# Chronos-Pad-EasyEDApro-Save.net
KiCad netlist of a schematic drawn in EasyEDA Pro
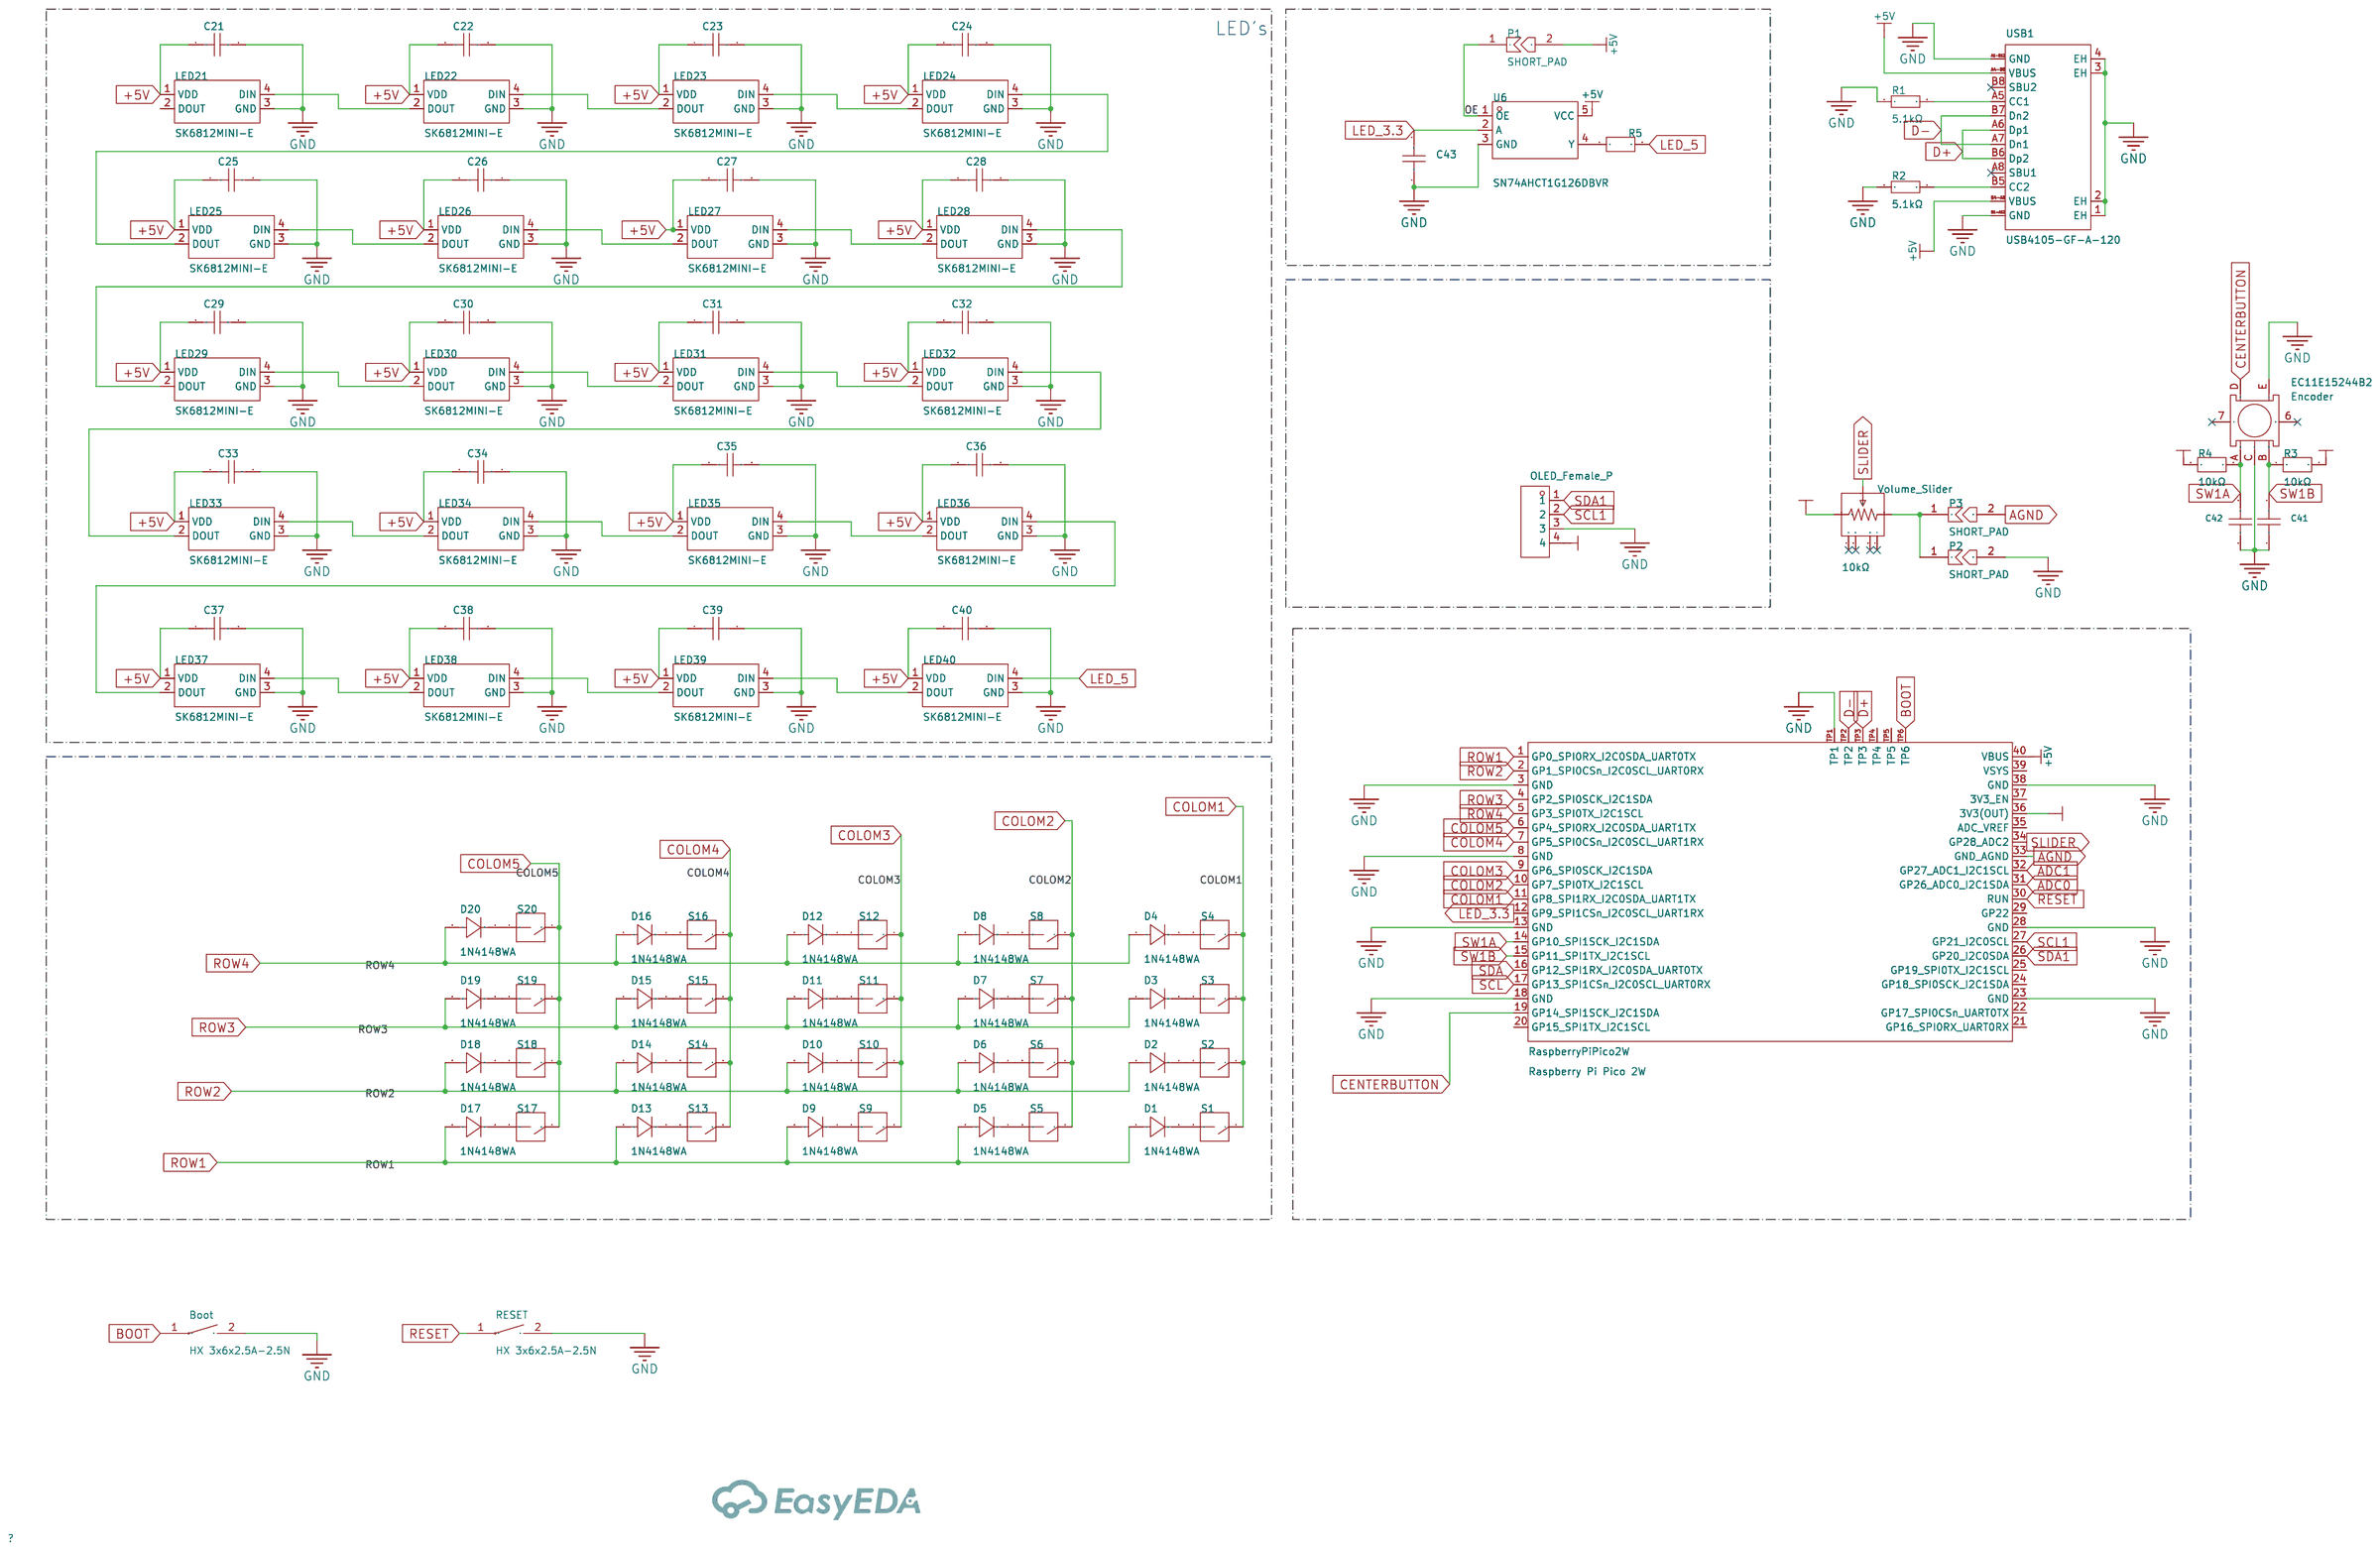
[diagram p0: schematic sheet]

(export (version "E")
  (design (tool "Eeschema 10.0.6"))
  (components
    (comp (ref "Boot")
      (value "HX 3x6x2.5A-2.5N")
      (footprint "easyedapro:SW-SMD_HX-TS-1101-C-W")
      (fields (field (name "Manufacturer") "hanxia(韩下)"))
      (libsource (lib "easyedapro") (part "HX TS-1101-C-W"))
    )
    (comp (ref "C21")
      (value "100nF")
      (footprint "easyedapro:C0603")
      (description "Capacitance:100nF Tolerance:±10% Tolerance:±10% Voltage Rating:50V Temperature Coefficient:X7R")
      (fields
        (field (name "Manufacturer Part") "CC0805KRX7R9BB104")
        (field (name "Manufacturer") "YAGEO(国巨)")
      )
      (libsource (lib "easyedapro") (part "NL0603B104M500CPBN"))
    )
    (comp (ref "C22")
      (value "100nF")
      (footprint "easyedapro:C0603")
      (description "Capacitance:100nF Tolerance:±10% Tolerance:±10% Voltage Rating:50V Temperature Coefficient:X7R")
      (fields
        (field (name "Manufacturer Part") "CC0805KRX7R9BB104")
        (field (name "Manufacturer") "YAGEO(国巨)")
      )
      (libsource (lib "easyedapro") (part "NL0603B104M500CPBN"))
    )
    (comp (ref "C23")
      (value "100nF")
      (footprint "easyedapro:C0603")
      (description "Capacitance:100nF Tolerance:±10% Tolerance:±10% Voltage Rating:50V Temperature Coefficient:X7R")
      (fields
        (field (name "Manufacturer Part") "CC0805KRX7R9BB104")
        (field (name "Manufacturer") "YAGEO(国巨)")
      )
      (libsource (lib "easyedapro") (part "NL0603B104M500CPBN"))
    )
    (comp (ref "C24")
      (value "100nF")
      (footprint "easyedapro:C0603")
      (description "Capacitance:100nF Tolerance:±10% Tolerance:±10% Voltage Rating:50V Temperature Coefficient:X7R")
      (fields
        (field (name "Manufacturer Part") "CC0805KRX7R9BB104")
        (field (name "Manufacturer") "YAGEO(国巨)")
      )
      (libsource (lib "easyedapro") (part "NL0603B104M500CPBN"))
    )
    (comp (ref "C25")
      (value "100nF")
      (footprint "easyedapro:C0603")
      (description "Capacitance:100nF Tolerance:±10% Tolerance:±10% Voltage Rating:50V Temperature Coefficient:X7R")
      (fields
        (field (name "Manufacturer Part") "CC0805KRX7R9BB104")
        (field (name "Manufacturer") "YAGEO(国巨)")
      )
      (libsource (lib "easyedapro") (part "NL0603B104M500CPBN"))
    )
    (comp (ref "C26")
      (value "100nF")
      (footprint "easyedapro:C0603")
      (description "Capacitance:100nF Tolerance:±10% Tolerance:±10% Voltage Rating:50V Temperature Coefficient:X7R")
      (fields
        (field (name "Manufacturer Part") "CC0805KRX7R9BB104")
        (field (name "Manufacturer") "YAGEO(国巨)")
      )
      (libsource (lib "easyedapro") (part "NL0603B104M500CPBN"))
    )
    (comp (ref "C27")
      (value "100nF")
      (footprint "easyedapro:C0603")
      (description "Capacitance:100nF Tolerance:±10% Tolerance:±10% Voltage Rating:50V Temperature Coefficient:X7R")
      (fields
        (field (name "Manufacturer Part") "CC0805KRX7R9BB104")
        (field (name "Manufacturer") "YAGEO(国巨)")
      )
      (libsource (lib "easyedapro") (part "NL0603B104M500CPBN"))
    )
    (comp (ref "C28")
      (value "100nF")
      (footprint "easyedapro:C0603")
      (description "Capacitance:100nF Tolerance:±10% Tolerance:±10% Voltage Rating:50V Temperature Coefficient:X7R")
      (fields
        (field (name "Manufacturer Part") "CC0805KRX7R9BB104")
        (field (name "Manufacturer") "YAGEO(国巨)")
      )
      (libsource (lib "easyedapro") (part "NL0603B104M500CPBN"))
    )
    (comp (ref "C29")
      (value "100nF")
      (footprint "easyedapro:C0603")
      (description "Capacitance:100nF Tolerance:±10% Tolerance:±10% Voltage Rating:50V Temperature Coefficient:X7R")
      (fields
        (field (name "Manufacturer Part") "CC0805KRX7R9BB104")
        (field (name "Manufacturer") "YAGEO(国巨)")
      )
      (libsource (lib "easyedapro") (part "NL0603B104M500CPBN"))
    )
    (comp (ref "C30")
      (value "100nF")
      (footprint "easyedapro:C0603")
      (description "Capacitance:100nF Tolerance:±10% Tolerance:±10% Voltage Rating:50V Temperature Coefficient:X7R")
      (fields
        (field (name "Manufacturer Part") "CC0805KRX7R9BB104")
        (field (name "Manufacturer") "YAGEO(国巨)")
      )
      (libsource (lib "easyedapro") (part "NL0603B104M500CPBN"))
    )
    (comp (ref "C31")
      (value "100nF")
      (footprint "easyedapro:C0603")
      (description "Capacitance:100nF Tolerance:±10% Tolerance:±10% Voltage Rating:50V Temperature Coefficient:X7R")
      (fields
        (field (name "Manufacturer Part") "CC0805KRX7R9BB104")
        (field (name "Manufacturer") "YAGEO(国巨)")
      )
      (libsource (lib "easyedapro") (part "NL0603B104M500CPBN"))
    )
    (comp (ref "C32")
      (value "100nF")
      (footprint "easyedapro:C0603")
      (description "Capacitance:100nF Tolerance:±10% Tolerance:±10% Voltage Rating:50V Temperature Coefficient:X7R")
      (fields
        (field (name "Manufacturer Part") "CC0805KRX7R9BB104")
        (field (name "Manufacturer") "YAGEO(国巨)")
      )
      (libsource (lib "easyedapro") (part "NL0603B104M500CPBN"))
    )
    (comp (ref "C33")
      (value "100nF")
      (footprint "easyedapro:C0603")
      (description "Capacitance:100nF Tolerance:±10% Tolerance:±10% Voltage Rating:50V Temperature Coefficient:X7R")
      (fields
        (field (name "Manufacturer Part") "CC0805KRX7R9BB104")
        (field (name "Manufacturer") "YAGEO(国巨)")
      )
      (libsource (lib "easyedapro") (part "NL0603B104M500CPBN"))
    )
    (comp (ref "C34")
      (value "100nF")
      (footprint "easyedapro:C0603")
      (description "Capacitance:100nF Tolerance:±10% Tolerance:±10% Voltage Rating:50V Temperature Coefficient:X7R")
      (fields
        (field (name "Manufacturer Part") "CC0805KRX7R9BB104")
        (field (name "Manufacturer") "YAGEO(国巨)")
      )
      (libsource (lib "easyedapro") (part "NL0603B104M500CPBN"))
    )
    (comp (ref "C35")
      (value "100nF")
      (footprint "easyedapro:C0603")
      (description "Capacitance:100nF Tolerance:±10% Tolerance:±10% Voltage Rating:50V Temperature Coefficient:X7R")
      (fields
        (field (name "Manufacturer Part") "CC0805KRX7R9BB104")
        (field (name "Manufacturer") "YAGEO(国巨)")
      )
      (libsource (lib "easyedapro") (part "NL0603B104M500CPBN"))
    )
    (comp (ref "C36")
      (value "100nF")
      (footprint "easyedapro:C0603")
      (description "Capacitance:100nF Tolerance:±10% Tolerance:±10% Voltage Rating:50V Temperature Coefficient:X7R")
      (fields
        (field (name "Manufacturer Part") "CC0805KRX7R9BB104")
        (field (name "Manufacturer") "YAGEO(国巨)")
      )
      (libsource (lib "easyedapro") (part "NL0603B104M500CPBN"))
    )
    (comp (ref "C37")
      (value "100nF")
      (footprint "easyedapro:C0603")
      (description "Capacitance:100nF Tolerance:±10% Tolerance:±10% Voltage Rating:50V Temperature Coefficient:X7R")
      (fields
        (field (name "Manufacturer Part") "CC0805KRX7R9BB104")
        (field (name "Manufacturer") "YAGEO(国巨)")
      )
      (libsource (lib "easyedapro") (part "NL0603B104M500CPBN"))
    )
    (comp (ref "C38")
      (value "100nF")
      (footprint "easyedapro:C0603")
      (description "Capacitance:100nF Tolerance:±10% Tolerance:±10% Voltage Rating:50V Temperature Coefficient:X7R")
      (fields
        (field (name "Manufacturer Part") "CC0805KRX7R9BB104")
        (field (name "Manufacturer") "YAGEO(国巨)")
      )
      (libsource (lib "easyedapro") (part "NL0603B104M500CPBN"))
    )
    (comp (ref "C39")
      (value "100nF")
      (footprint "easyedapro:C0603")
      (description "Capacitance:100nF Tolerance:±10% Tolerance:±10% Voltage Rating:50V Temperature Coefficient:X7R")
      (fields
        (field (name "Manufacturer Part") "CC0805KRX7R9BB104")
        (field (name "Manufacturer") "YAGEO(国巨)")
      )
      (libsource (lib "easyedapro") (part "NL0603B104M500CPBN"))
    )
    (comp (ref "C40")
      (value "100nF")
      (footprint "easyedapro:C0603")
      (description "Capacitance:100nF Tolerance:±10% Tolerance:±10% Voltage Rating:50V Temperature Coefficient:X7R")
      (fields
        (field (name "Manufacturer Part") "CC0805KRX7R9BB104")
        (field (name "Manufacturer") "YAGEO(国巨)")
      )
      (libsource (lib "easyedapro") (part "NL0603B104M500CPBN"))
    )
    (comp (ref "C41")
      (value "100nF")
      (footprint "easyedapro:C0805")
      (description "Capacitance:100nF Tolerance:±10% Tolerance:±10% Voltage Rating:50V Temperature Coefficient:X7R")
      (fields
        (field (name "Manufacturer Part") "CC0805KRX7R9BB104")
        (field (name "Manufacturer") "YAGEO(国巨)")
      )
      (libsource (lib "easyedapro") (part "CC0805JRX7R9BB103"))
    )
    (comp (ref "C42")
      (value "100nF")
      (footprint "easyedapro:C0805")
      (description "Capacitance:100nF Tolerance:±10% Tolerance:±10% Voltage Rating:50V Temperature Coefficient:X7R")
      (fields
        (field (name "Manufacturer Part") "CC0805KRX7R9BB104")
        (field (name "Manufacturer") "YAGEO(国巨)")
      )
      (libsource (lib "easyedapro") (part "CC0805JRX7R9BB103"))
    )
    (comp (ref "C43")
      (value "100nF")
      (footprint "easyedapro:C0603")
      (description "Capacitance:100nF Tolerance:±10% Tolerance:±10% Voltage Rating:50V Temperature Coefficient:X7R")
      (fields
        (field (name "Manufacturer Part") "CC0805KRX7R9BB104")
        (field (name "Manufacturer") "YAGEO(国巨)")
      )
      (libsource (lib "easyedapro") (part "NL0603B104M500CPBN"))
    )
    (comp (ref "D1")
      (value "1N4148WA")
      (footprint "easyedapro:SOD-323_L1.7-W1.3-LS2.7-RD")
      (fields (field (name "Manufacturer") "PJSEMI(平晶微)"))
      (libsource (lib "easyedapro") (part "1N4148WS_C5381436"))
    )
    (comp (ref "D2")
      (value "1N4148WA")
      (footprint "easyedapro:SOD-323_L1.7-W1.3-LS2.7-RD")
      (fields (field (name "Manufacturer") "PJSEMI(平晶微)"))
      (libsource (lib "easyedapro") (part "1N4148WS_C5381436"))
    )
    (comp (ref "D3")
      (value "1N4148WA")
      (footprint "easyedapro:SOD-323_L1.7-W1.3-LS2.7-RD")
      (fields (field (name "Manufacturer") "PJSEMI(平晶微)"))
      (libsource (lib "easyedapro") (part "1N4148WS_C5381436"))
    )
    (comp (ref "D4")
      (value "1N4148WA")
      (footprint "easyedapro:SOD-323_L1.7-W1.3-LS2.7-RD")
      (fields (field (name "Manufacturer") "PJSEMI(平晶微)"))
      (libsource (lib "easyedapro") (part "1N4148WS_C5381436"))
    )
    (comp (ref "D5")
      (value "1N4148WA")
      (footprint "easyedapro:SOD-323_L1.7-W1.3-LS2.7-RD")
      (fields (field (name "Manufacturer") "PJSEMI(平晶微)"))
      (libsource (lib "easyedapro") (part "1N4148WS_C5381436"))
    )
    (comp (ref "D6")
      (value "1N4148WA")
      (footprint "easyedapro:SOD-323_L1.7-W1.3-LS2.7-RD")
      (fields (field (name "Manufacturer") "PJSEMI(平晶微)"))
      (libsource (lib "easyedapro") (part "1N4148WS_C5381436"))
    )
    (comp (ref "D7")
      (value "1N4148WA")
      (footprint "easyedapro:SOD-323_L1.7-W1.3-LS2.7-RD")
      (fields (field (name "Manufacturer") "PJSEMI(平晶微)"))
      (libsource (lib "easyedapro") (part "1N4148WS_C5381436"))
    )
    (comp (ref "D8")
      (value "1N4148WA")
      (footprint "easyedapro:SOD-323_L1.7-W1.3-LS2.7-RD")
      (fields (field (name "Manufacturer") "PJSEMI(平晶微)"))
      (libsource (lib "easyedapro") (part "1N4148WS_C5381436"))
    )
    (comp (ref "D9")
      (value "1N4148WA")
      (footprint "easyedapro:SOD-323_L1.7-W1.3-LS2.7-RD")
      (fields (field (name "Manufacturer") "PJSEMI(平晶微)"))
      (libsource (lib "easyedapro") (part "1N4148WS_C5381436"))
    )
    (comp (ref "D10")
      (value "1N4148WA")
      (footprint "easyedapro:SOD-323_L1.7-W1.3-LS2.7-RD")
      (fields (field (name "Manufacturer") "PJSEMI(平晶微)"))
      (libsource (lib "easyedapro") (part "1N4148WS_C5381436"))
    )
    (comp (ref "D11")
      (value "1N4148WA")
      (footprint "easyedapro:SOD-323_L1.7-W1.3-LS2.7-RD")
      (fields (field (name "Manufacturer") "PJSEMI(平晶微)"))
      (libsource (lib "easyedapro") (part "1N4148WS_C5381436"))
    )
    (comp (ref "D12")
      (value "1N4148WA")
      (footprint "easyedapro:SOD-323_L1.7-W1.3-LS2.7-RD")
      (fields (field (name "Manufacturer") "PJSEMI(平晶微)"))
      (libsource (lib "easyedapro") (part "1N4148WS_C5381436"))
    )
    (comp (ref "D13")
      (value "1N4148WA")
      (footprint "easyedapro:SOD-323_L1.7-W1.3-LS2.7-RD")
      (fields (field (name "Manufacturer") "PJSEMI(平晶微)"))
      (libsource (lib "easyedapro") (part "1N4148WS_C5381436"))
    )
    (comp (ref "D14")
      (value "1N4148WA")
      (footprint "easyedapro:SOD-323_L1.7-W1.3-LS2.7-RD")
      (fields (field (name "Manufacturer") "PJSEMI(平晶微)"))
      (libsource (lib "easyedapro") (part "1N4148WS_C5381436"))
    )
    (comp (ref "D15")
      (value "1N4148WA")
      (footprint "easyedapro:SOD-323_L1.7-W1.3-LS2.7-RD")
      (fields (field (name "Manufacturer") "PJSEMI(平晶微)"))
      (libsource (lib "easyedapro") (part "1N4148WS_C5381436"))
    )
    (comp (ref "D16")
      (value "1N4148WA")
      (footprint "easyedapro:SOD-323_L1.7-W1.3-LS2.7-RD")
      (fields (field (name "Manufacturer") "PJSEMI(平晶微)"))
      (libsource (lib "easyedapro") (part "1N4148WS_C5381436"))
    )
    (comp (ref "D17")
      (value "1N4148WA")
      (footprint "easyedapro:SOD-323_L1.7-W1.3-LS2.7-RD")
      (fields (field (name "Manufacturer") "PJSEMI(平晶微)"))
      (libsource (lib "easyedapro") (part "1N4148WS_C5381436"))
    )
    (comp (ref "D18")
      (value "1N4148WA")
      (footprint "easyedapro:SOD-323_L1.7-W1.3-LS2.7-RD")
      (fields (field (name "Manufacturer") "PJSEMI(平晶微)"))
      (libsource (lib "easyedapro") (part "1N4148WS_C5381436"))
    )
    (comp (ref "D19")
      (value "1N4148WA")
      (footprint "easyedapro:SOD-323_L1.7-W1.3-LS2.7-RD")
      (fields (field (name "Manufacturer") "PJSEMI(平晶微)"))
      (libsource (lib "easyedapro") (part "1N4148WS_C5381436"))
    )
    (comp (ref "D20")
      (value "1N4148WA")
      (footprint "easyedapro:SOD-323_L1.7-W1.3-LS2.7-RD")
      (fields (field (name "Manufacturer") "PJSEMI(平晶微)"))
      (libsource (lib "easyedapro") (part "1N4148WS_C5381436"))
    )
    (comp (ref "Encoder")
      (value "EC11E15244B2")
      (footprint "easyedapro:SW-TH_EC11XXXXXXXX")
      (fields (field (name "Manufacturer") "ALPSALPINE(阿尔卑斯阿尔派)"))
      (libsource (lib "easyedapro") (part "EC11E15204A3"))
    )
    (comp (ref "LED21")
      (value "SK6812MINI-E")
      (footprint "easyedapro:LED-SMD_L3.2-W2.8-LS5.9_SK6812MINI-E")
      (fields (field (name "Manufacturer") "欧思科光电"))
      (libsource (lib "easyedapro") (part "SK6812MINI-E_C5149201"))
    )
    (comp (ref "LED22")
      (value "SK6812MINI-E")
      (footprint "easyedapro:LED-SMD_L3.2-W2.8-LS5.9_SK6812MINI-E")
      (fields (field (name "Manufacturer") "欧思科光电"))
      (libsource (lib "easyedapro") (part "SK6812MINI-E_C5149201"))
    )
    (comp (ref "LED23")
      (value "SK6812MINI-E")
      (footprint "easyedapro:LED-SMD_L3.2-W2.8-LS5.9_SK6812MINI-E")
      (fields (field (name "Manufacturer") "欧思科光电"))
      (libsource (lib "easyedapro") (part "SK6812MINI-E_C5149201"))
    )
    (comp (ref "LED24")
      (value "SK6812MINI-E")
      (footprint "easyedapro:LED-SMD_L3.2-W2.8-LS5.9_SK6812MINI-E")
      (fields (field (name "Manufacturer") "欧思科光电"))
      (libsource (lib "easyedapro") (part "SK6812MINI-E_C5149201"))
    )
    (comp (ref "LED25")
      (value "SK6812MINI-E")
      (footprint "easyedapro:LED-SMD_L3.2-W2.8-LS5.9_SK6812MINI-E")
      (fields (field (name "Manufacturer") "欧思科光电"))
      (libsource (lib "easyedapro") (part "SK6812MINI-E_C5149201"))
    )
    (comp (ref "LED26")
      (value "SK6812MINI-E")
      (footprint "easyedapro:LED-SMD_L3.2-W2.8-LS5.9_SK6812MINI-E")
      (fields (field (name "Manufacturer") "欧思科光电"))
      (libsource (lib "easyedapro") (part "SK6812MINI-E_C5149201"))
    )
    (comp (ref "LED27")
      (value "SK6812MINI-E")
      (footprint "easyedapro:LED-SMD_L3.2-W2.8-LS5.9_SK6812MINI-E")
      (fields (field (name "Manufacturer") "欧思科光电"))
      (libsource (lib "easyedapro") (part "SK6812MINI-E_C5149201"))
    )
    (comp (ref "LED28")
      (value "SK6812MINI-E")
      (footprint "easyedapro:LED-SMD_L3.2-W2.8-LS5.9_SK6812MINI-E")
      (fields (field (name "Manufacturer") "欧思科光电"))
      (libsource (lib "easyedapro") (part "SK6812MINI-E_C5149201"))
    )
    (comp (ref "LED29")
      (value "SK6812MINI-E")
      (footprint "easyedapro:LED-SMD_L3.2-W2.8-LS5.9_SK6812MINI-E")
      (fields (field (name "Manufacturer") "欧思科光电"))
      (libsource (lib "easyedapro") (part "SK6812MINI-E_C5149201"))
    )
    (comp (ref "LED30")
      (value "SK6812MINI-E")
      (footprint "easyedapro:LED-SMD_L3.2-W2.8-LS5.9_SK6812MINI-E")
      (fields (field (name "Manufacturer") "欧思科光电"))
      (libsource (lib "easyedapro") (part "SK6812MINI-E_C5149201"))
    )
    (comp (ref "LED31")
      (value "SK6812MINI-E")
      (footprint "easyedapro:LED-SMD_L3.2-W2.8-LS5.9_SK6812MINI-E")
      (fields (field (name "Manufacturer") "欧思科光电"))
      (libsource (lib "easyedapro") (part "SK6812MINI-E_C5149201"))
    )
    (comp (ref "LED32")
      (value "SK6812MINI-E")
      (footprint "easyedapro:LED-SMD_L3.2-W2.8-LS5.9_SK6812MINI-E")
      (fields (field (name "Manufacturer") "欧思科光电"))
      (libsource (lib "easyedapro") (part "SK6812MINI-E_C5149201"))
    )
    (comp (ref "LED33")
      (value "SK6812MINI-E")
      (footprint "easyedapro:LED-SMD_L3.2-W2.8-LS5.9_SK6812MINI-E")
      (fields (field (name "Manufacturer") "欧思科光电"))
      (libsource (lib "easyedapro") (part "SK6812MINI-E_C5149201"))
    )
    (comp (ref "LED34")
      (value "SK6812MINI-E")
      (footprint "easyedapro:LED-SMD_L3.2-W2.8-LS5.9_SK6812MINI-E")
      (fields (field (name "Manufacturer") "欧思科光电"))
      (libsource (lib "easyedapro") (part "SK6812MINI-E_C5149201"))
    )
    (comp (ref "LED35")
      (value "SK6812MINI-E")
      (footprint "easyedapro:LED-SMD_L3.2-W2.8-LS5.9_SK6812MINI-E")
      (fields (field (name "Manufacturer") "欧思科光电"))
      (libsource (lib "easyedapro") (part "SK6812MINI-E_C5149201"))
    )
    (comp (ref "LED36")
      (value "SK6812MINI-E")
      (footprint "easyedapro:LED-SMD_L3.2-W2.8-LS5.9_SK6812MINI-E")
      (fields (field (name "Manufacturer") "欧思科光电"))
      (libsource (lib "easyedapro") (part "SK6812MINI-E_C5149201"))
    )
    (comp (ref "LED37")
      (value "SK6812MINI-E")
      (footprint "easyedapro:LED-SMD_L3.2-W2.8-LS5.9_SK6812MINI-E")
      (fields (field (name "Manufacturer") "欧思科光电"))
      (libsource (lib "easyedapro") (part "SK6812MINI-E_C5149201"))
    )
    (comp (ref "LED38")
      (value "SK6812MINI-E")
      (footprint "easyedapro:LED-SMD_L3.2-W2.8-LS5.9_SK6812MINI-E")
      (fields (field (name "Manufacturer") "欧思科光电"))
      (libsource (lib "easyedapro") (part "SK6812MINI-E_C5149201"))
    )
    (comp (ref "LED39")
      (value "SK6812MINI-E")
      (footprint "easyedapro:LED-SMD_L3.2-W2.8-LS5.9_SK6812MINI-E")
      (fields (field (name "Manufacturer") "欧思科光电"))
      (libsource (lib "easyedapro") (part "SK6812MINI-E_C5149201"))
    )
    (comp (ref "LED40")
      (value "SK6812MINI-E")
      (footprint "easyedapro:LED-SMD_L3.2-W2.8-LS5.9_SK6812MINI-E")
      (fields (field (name "Manufacturer") "欧思科光电"))
      (libsource (lib "easyedapro") (part "SK6812MINI-E_C5149201"))
    )
    (comp (ref "OLED_Female_P")
      (value "~")
      (footprint "easyedapro:CONN-TH_4P-P2.50-XH2.54-4P")
      (fields (field (name "Manufacturer Part") "XH-2.54-4P"))
      (libsource (lib "easyedapro") (part "XH-2.54-4P"))
    )
    (comp (ref "P1")
      (value "SHORT_PAD")
      (footprint "easyedapro:SHORT_PAD")
      (libsource (lib "easyedapro") (part "SHORT_PAD"))
    )
    (comp (ref "P2")
      (value "SHORT_PAD")
      (footprint "easyedapro:SHORT_PAD")
      (libsource (lib "easyedapro") (part "SHORT_PAD"))
    )
    (comp (ref "P3")
      (value "SHORT_PAD")
      (footprint "easyedapro:SHORT_PAD")
      (libsource (lib "easyedapro") (part "SHORT_PAD"))
    )
    (comp (ref "R1")
      (value "5.1kΩ")
      (footprint "easyedapro:R0805")
      (fields (field (name "Manufacturer Part") "MCR10EZPF5101") (field (name "Manufacturer") "ROHM(罗姆)"))
      (libsource (lib "easyedapro") (part "MCR10EZPF5101"))
    )
    (comp (ref "R2")
      (value "5.1kΩ")
      (footprint "easyedapro:R0805")
      (fields (field (name "Manufacturer Part") "MCR10EZPF5101") (field (name "Manufacturer") "ROHM(罗姆)"))
      (libsource (lib "easyedapro") (part "MCR10EZPF5101"))
    )
    (comp (ref "R3")
      (value "10kΩ")
      (footprint "easyedapro:R0805")
      (fields (field (name "Manufacturer Part") "SCR0805J10K") (field (name "Manufacturer") "VO(翔胜)"))
      (libsource (lib "easyedapro") (part "SCR0805J10K"))
    )
    (comp (ref "R4")
      (value "10kΩ")
      (footprint "easyedapro:R0805")
      (fields (field (name "Manufacturer Part") "SCR0805J10K") (field (name "Manufacturer") "VO(翔胜)"))
      (libsource (lib "easyedapro") (part "SCR0805J10K"))
    )
    (comp (ref "R5")
      (value "300Ω")
      (footprint "easyedapro:R0805")
      (fields
        (field (name "Manufacturer Part") "CRCW0805300RFKEA")
        (field (name "Manufacturer") "VISHAY(威世)")
      )
      (libsource (lib "easyedapro") (part "CRCW0805300RFKEA"))
    )
    (comp (ref "RaspberryPiPico2W")
      (value "Raspberry Pi Pico 2W")
      (footprint "easyedapro:COMM-SMD_L51.0-W21.0-P2.54_PICOW")
      (fields (field (name "Manufacturer") "Raspberry Pi(树莓派)"))
      (libsource (lib "easyedapro") (part "RASPBERRY PI PICO 2W"))
    )
    (comp (ref "RESET")
      (value "HX 3x6x2.5A-2.5N")
      (footprint "easyedapro:SW-SMD_HX-TS-1101-C-W")
      (fields (field (name "Manufacturer") "hanxia(韩下)"))
      (libsource (lib "easyedapro") (part "HX TS-1101-C-W"))
    )
    (comp (ref "S1")
      (value "adafruit_electromech_KBD_SWITCH_KAILH_SOCKET_BOX_JADE_KAILH_SOCKET")
      (footprint "easyedapro:KAILH_SOCKET")
      (libsource (lib "easyedapro") (part "adafruit_electromech_KBD_SWITCH_KAILH_SOCKET_BOX_JADE_KAILH_SOCKET"))
    )
    (comp (ref "S2")
      (value "adafruit_electromech_KBD_SWITCH_KAILH_SOCKET_BOX_JADE_KAILH_SOCKET")
      (footprint "easyedapro:KAILH_SOCKET")
      (libsource (lib "easyedapro") (part "adafruit_electromech_KBD_SWITCH_KAILH_SOCKET_BOX_JADE_KAILH_SOCKET"))
    )
    (comp (ref "S3")
      (value "adafruit_electromech_KBD_SWITCH_KAILH_SOCKET_BOX_JADE_KAILH_SOCKET")
      (footprint "easyedapro:KAILH_SOCKET")
      (libsource (lib "easyedapro") (part "adafruit_electromech_KBD_SWITCH_KAILH_SOCKET_BOX_JADE_KAILH_SOCKET"))
    )
    (comp (ref "S4")
      (value "adafruit_electromech_KBD_SWITCH_KAILH_SOCKET_BOX_JADE_KAILH_SOCKET")
      (footprint "easyedapro:KAILH_SOCKET")
      (libsource (lib "easyedapro") (part "adafruit_electromech_KBD_SWITCH_KAILH_SOCKET_BOX_JADE_KAILH_SOCKET"))
    )
    (comp (ref "S5")
      (value "adafruit_electromech_KBD_SWITCH_KAILH_SOCKET_BOX_JADE_KAILH_SOCKET")
      (footprint "easyedapro:KAILH_SOCKET")
      (libsource (lib "easyedapro") (part "adafruit_electromech_KBD_SWITCH_KAILH_SOCKET_BOX_JADE_KAILH_SOCKET"))
    )
    (comp (ref "S6")
      (value "adafruit_electromech_KBD_SWITCH_KAILH_SOCKET_BOX_JADE_KAILH_SOCKET")
      (footprint "easyedapro:KAILH_SOCKET")
      (libsource (lib "easyedapro") (part "adafruit_electromech_KBD_SWITCH_KAILH_SOCKET_BOX_JADE_KAILH_SOCKET"))
    )
    (comp (ref "S7")
      (value "adafruit_electromech_KBD_SWITCH_KAILH_SOCKET_BOX_JADE_KAILH_SOCKET")
      (footprint "easyedapro:KAILH_SOCKET")
      (libsource (lib "easyedapro") (part "adafruit_electromech_KBD_SWITCH_KAILH_SOCKET_BOX_JADE_KAILH_SOCKET"))
    )
    (comp (ref "S8")
      (value "adafruit_electromech_KBD_SWITCH_KAILH_SOCKET_BOX_JADE_KAILH_SOCKET")
      (footprint "easyedapro:KAILH_SOCKET")
      (libsource (lib "easyedapro") (part "adafruit_electromech_KBD_SWITCH_KAILH_SOCKET_BOX_JADE_KAILH_SOCKET"))
    )
    (comp (ref "S9")
      (value "adafruit_electromech_KBD_SWITCH_KAILH_SOCKET_BOX_JADE_KAILH_SOCKET")
      (footprint "easyedapro:KAILH_SOCKET")
      (libsource (lib "easyedapro") (part "adafruit_electromech_KBD_SWITCH_KAILH_SOCKET_BOX_JADE_KAILH_SOCKET"))
    )
    (comp (ref "S10")
      (value "adafruit_electromech_KBD_SWITCH_KAILH_SOCKET_BOX_JADE_KAILH_SOCKET")
      (footprint "easyedapro:KAILH_SOCKET")
      (libsource (lib "easyedapro") (part "adafruit_electromech_KBD_SWITCH_KAILH_SOCKET_BOX_JADE_KAILH_SOCKET"))
    )
    (comp (ref "S11")
      (value "adafruit_electromech_KBD_SWITCH_KAILH_SOCKET_BOX_JADE_KAILH_SOCKET")
      (footprint "easyedapro:KAILH_SOCKET")
      (libsource (lib "easyedapro") (part "adafruit_electromech_KBD_SWITCH_KAILH_SOCKET_BOX_JADE_KAILH_SOCKET"))
    )
    (comp (ref "S12")
      (value "adafruit_electromech_KBD_SWITCH_KAILH_SOCKET_BOX_JADE_KAILH_SOCKET")
      (footprint "easyedapro:KAILH_SOCKET")
      (libsource (lib "easyedapro") (part "adafruit_electromech_KBD_SWITCH_KAILH_SOCKET_BOX_JADE_KAILH_SOCKET"))
    )
    (comp (ref "S13")
      (value "adafruit_electromech_KBD_SWITCH_KAILH_SOCKET_BOX_JADE_KAILH_SOCKET")
      (footprint "easyedapro:KAILH_SOCKET")
      (libsource (lib "easyedapro") (part "adafruit_electromech_KBD_SWITCH_KAILH_SOCKET_BOX_JADE_KAILH_SOCKET"))
    )
    (comp (ref "S14")
      (value "adafruit_electromech_KBD_SWITCH_KAILH_SOCKET_BOX_JADE_KAILH_SOCKET")
      (footprint "easyedapro:KAILH_SOCKET")
      (libsource (lib "easyedapro") (part "adafruit_electromech_KBD_SWITCH_KAILH_SOCKET_BOX_JADE_KAILH_SOCKET"))
    )
    (comp (ref "S15")
      (value "adafruit_electromech_KBD_SWITCH_KAILH_SOCKET_BOX_JADE_KAILH_SOCKET")
      (footprint "easyedapro:KAILH_SOCKET")
      (libsource (lib "easyedapro") (part "adafruit_electromech_KBD_SWITCH_KAILH_SOCKET_BOX_JADE_KAILH_SOCKET"))
    )
    (comp (ref "S16")
      (value "adafruit_electromech_KBD_SWITCH_KAILH_SOCKET_BOX_JADE_KAILH_SOCKET")
      (footprint "easyedapro:KAILH_SOCKET")
      (libsource (lib "easyedapro") (part "adafruit_electromech_KBD_SWITCH_KAILH_SOCKET_BOX_JADE_KAILH_SOCKET"))
    )
    (comp (ref "S17")
      (value "adafruit_electromech_KBD_SWITCH_KAILH_SOCKET_BOX_JADE_KAILH_SOCKET")
      (footprint "easyedapro:KAILH_SOCKET")
      (libsource (lib "easyedapro") (part "adafruit_electromech_KBD_SWITCH_KAILH_SOCKET_BOX_JADE_KAILH_SOCKET"))
    )
    (comp (ref "S18")
      (value "adafruit_electromech_KBD_SWITCH_KAILH_SOCKET_BOX_JADE_KAILH_SOCKET")
      (footprint "easyedapro:KAILH_SOCKET")
      (libsource (lib "easyedapro") (part "adafruit_electromech_KBD_SWITCH_KAILH_SOCKET_BOX_JADE_KAILH_SOCKET"))
    )
    (comp (ref "S19")
      (value "adafruit_electromech_KBD_SWITCH_KAILH_SOCKET_BOX_JADE_KAILH_SOCKET")
      (footprint "easyedapro:KAILH_SOCKET")
      (libsource (lib "easyedapro") (part "adafruit_electromech_KBD_SWITCH_KAILH_SOCKET_BOX_JADE_KAILH_SOCKET"))
    )
    (comp (ref "S20")
      (value "adafruit_electromech_KBD_SWITCH_KAILH_SOCKET_BOX_JADE_KAILH_SOCKET")
      (footprint "easyedapro:KAILH_SOCKET")
      (libsource (lib "easyedapro") (part "adafruit_electromech_KBD_SWITCH_KAILH_SOCKET_BOX_JADE_KAILH_SOCKET"))
    )
    (comp (ref "U6")
      (value "SN74AHCT1G126DBVR")
      (footprint "easyedapro:SOT-23-5_L3.0-W1.7-P0.95-LS2.8-BR")
      (fields (field (name "Manufacturer") "TI(德州仪器)"))
      (libsource (lib "easyedapro") (part "SN74AHCT1G126DBVR"))
    )
    (comp (ref "USB1")
      (value "USB4105-GF-A-120")
      (footprint "easyedapro:USB-C-SMD_MC-311D")
      (fields (field (name "Manufacturer") "GCT"))
      (libsource (lib "easyedapro") (part "USB4105-GF-A-120"))
    )
    (comp (ref "Volume_Slider")
      (value "10kΩ")
      (footprint "easyedapro:RES-ADJ-TH_PTA6043-2015DPB103")
      (description "Resistance:10kΩ Tolerance:±20% Tolerance:±20% Power(Watts):250mW")
      (fields (field (name "Manufacturer Part") "PTA6043-2015DPB103") (field (name "Manufacturer") "BOURNS"))
      (libsource (lib "easyedapro") (part "PTA6043-2015DPB103"))
    )
  )
  (nets
    (net (code "1") (name "+3.3V") (class "Default")
      (node (ref "OLED_Female_P") (pin "4") (pinfunction "4_4") (pintype "input"))
      (node (ref "R3") (pin "2") (pinfunction "2_2") (pintype "unspecified"))
      (node (ref "R4") (pin "1") (pinfunction "1_1") (pintype "unspecified"))
      (node (ref "RaspberryPiPico2W") (pin "36") (pinfunction "3V3(OUT)_36") (pintype "unspecified"))
      (node (ref "Volume_Slider") (pin "3") (pinfunction "3_3") (pintype "unspecified"))
    )
    (net (code "2") (name "+5V") (class "Default")
      (node (ref "C21") (pin "1") (pinfunction "1_1") (pintype "unspecified"))
      (node (ref "C22") (pin "1") (pinfunction "1_1") (pintype "unspecified"))
      (node (ref "C23") (pin "1") (pinfunction "1_1") (pintype "unspecified"))
      (node (ref "C24") (pin "1") (pinfunction "1_1") (pintype "unspecified"))
      (node (ref "C25") (pin "1") (pinfunction "1_1") (pintype "unspecified"))
      (node (ref "C26") (pin "1") (pinfunction "1_1") (pintype "unspecified"))
      (node (ref "C27") (pin "1") (pinfunction "1_1") (pintype "unspecified"))
      (node (ref "C28") (pin "1") (pinfunction "1_1") (pintype "unspecified"))
      (node (ref "C29") (pin "1") (pinfunction "1_1") (pintype "unspecified"))
      (node (ref "C30") (pin "1") (pinfunction "1_1") (pintype "unspecified"))
      (node (ref "C31") (pin "1") (pinfunction "1_1") (pintype "unspecified"))
      (node (ref "C32") (pin "1") (pinfunction "1_1") (pintype "unspecified"))
      (node (ref "C33") (pin "1") (pinfunction "1_1") (pintype "unspecified"))
      (node (ref "C34") (pin "1") (pinfunction "1_1") (pintype "unspecified"))
      (node (ref "C35") (pin "1") (pinfunction "1_1") (pintype "unspecified"))
      (node (ref "C36") (pin "1") (pinfunction "1_1") (pintype "unspecified"))
      (node (ref "C37") (pin "1") (pinfunction "1_1") (pintype "unspecified"))
      (node (ref "C38") (pin "1") (pinfunction "1_1") (pintype "unspecified"))
      (node (ref "C39") (pin "1") (pinfunction "1_1") (pintype "unspecified"))
      (node (ref "C40") (pin "1") (pinfunction "1_1") (pintype "unspecified"))
      (node (ref "LED21") (pin "1") (pinfunction "VDD_1") (pintype "unspecified"))
      (node (ref "LED22") (pin "1") (pinfunction "VDD_1") (pintype "unspecified"))
      (node (ref "LED23") (pin "1") (pinfunction "VDD_1") (pintype "unspecified"))
      (node (ref "LED24") (pin "1") (pinfunction "VDD_1") (pintype "unspecified"))
      (node (ref "LED25") (pin "1") (pinfunction "VDD_1") (pintype "unspecified"))
      (node (ref "LED26") (pin "1") (pinfunction "VDD_1") (pintype "unspecified"))
      (node (ref "LED27") (pin "1") (pinfunction "VDD_1") (pintype "unspecified"))
      (node (ref "LED28") (pin "1") (pinfunction "VDD_1") (pintype "unspecified"))
      (node (ref "LED29") (pin "1") (pinfunction "VDD_1") (pintype "unspecified"))
      (node (ref "LED30") (pin "1") (pinfunction "VDD_1") (pintype "unspecified"))
      (node (ref "LED31") (pin "1") (pinfunction "VDD_1") (pintype "unspecified"))
      (node (ref "LED32") (pin "1") (pinfunction "VDD_1") (pintype "unspecified"))
      (node (ref "LED33") (pin "1") (pinfunction "VDD_1") (pintype "unspecified"))
      (node (ref "LED34") (pin "1") (pinfunction "VDD_1") (pintype "unspecified"))
      (node (ref "LED35") (pin "1") (pinfunction "VDD_1") (pintype "unspecified"))
      (node (ref "LED36") (pin "1") (pinfunction "VDD_1") (pintype "unspecified"))
      (node (ref "LED37") (pin "1") (pinfunction "VDD_1") (pintype "unspecified"))
      (node (ref "LED38") (pin "1") (pinfunction "VDD_1") (pintype "unspecified"))
      (node (ref "LED39") (pin "1") (pinfunction "VDD_1") (pintype "unspecified"))
      (node (ref "LED40") (pin "1") (pinfunction "VDD_1") (pintype "unspecified"))
      (node (ref "P1") (pin "2") (pinfunction "2_2") (pintype "input"))
      (node (ref "RaspberryPiPico2W") (pin "40") (pinfunction "VBUS_40") (pintype "unspecified"))
      (node (ref "U6") (pin "5") (pinfunction "VCC_5") (pintype "input"))
      (node (ref "USB1") (pin "A4-B9") (pinfunction "VBUS_A4-B9") (pintype "unspecified"))
      (node (ref "USB1") (pin "B4-A9") (pinfunction "VBUS_B4-A9") (pintype "unspecified"))
    )
    (net (code "3") (name "/OE") (class "Default")
      (node (ref "P1") (pin "1") (pinfunction "1_1") (pintype "input"))
      (node (ref "U6") (pin "1") (pinfunction "OE_1") (pintype "input"))
    )
    (net (code "4") (name "ADC0") (class "Default")
      (node (ref "RaspberryPiPico2W") (pin "31") (pinfunction "GP26_ADC0_I2C1SDA_31") (pintype "unspecified"))
    )
    (net (code "5") (name "ADC1") (class "Default")
      (node (ref "RaspberryPiPico2W") (pin "32") (pinfunction "GP27_ADC1_I2C1SCL_32") (pintype "unspecified"))
    )
    (net (code "6") (name "AGND") (class "Default")
      (node (ref "P3") (pin "2") (pinfunction "2_2") (pintype "input"))
      (node (ref "RaspberryPiPico2W") (pin "33") (pinfunction "GND_AGND_33") (pintype "unspecified"))
    )
    (net (code "7") (name "BOOT") (class "Default")
      (node (ref "Boot") (pin "1") (pinfunction "1_1") (pintype "unspecified"))
      (node (ref "RaspberryPiPico2W") (pin "TP6") (pinfunction "TP6_TP6") (pintype "unspecified"))
    )
    (net (code "8") (name "CENTERBUTTON") (class "Default")
      (node (ref "Encoder") (pin "D") (pinfunction "D_D") (pintype "unspecified"))
      (node (ref "RaspberryPiPico2W") (pin "19") (pinfunction "GP14_SPI1SCK_I2C1SDA_19") (pintype "unspecified"))
    )
    (net (code "9") (name "COLOM1") (class "Default")
      (node (ref "RaspberryPiPico2W") (pin "11") (pinfunction "GP8_SPI1RX_I2C0SDA_UART1TX_11") (pintype "unspecified"))
      (node (ref "S1") (pin "1") (pinfunction "1_1") (pintype "input"))
      (node (ref "S2") (pin "1") (pinfunction "1_1") (pintype "input"))
      (node (ref "S3") (pin "1") (pinfunction "1_1") (pintype "input"))
      (node (ref "S4") (pin "1") (pinfunction "1_1") (pintype "input"))
    )
    (net (code "10") (name "COLOM2") (class "Default")
      (node (ref "RaspberryPiPico2W") (pin "10") (pinfunction "GP7_SPI0TX_I2C1SCL_10") (pintype "unspecified"))
      (node (ref "S5") (pin "1") (pinfunction "1_1") (pintype "input"))
      (node (ref "S6") (pin "1") (pinfunction "1_1") (pintype "input"))
      (node (ref "S7") (pin "1") (pinfunction "1_1") (pintype "input"))
      (node (ref "S8") (pin "1") (pinfunction "1_1") (pintype "input"))
    )
    (net (code "11") (name "COLOM3") (class "Default")
      (node (ref "RaspberryPiPico2W") (pin "9") (pinfunction "GP6_SPI0SCK_I2C1SDA_9") (pintype "unspecified"))
      (node (ref "S10") (pin "1") (pinfunction "1_1") (pintype "input"))
      (node (ref "S11") (pin "1") (pinfunction "1_1") (pintype "input"))
      (node (ref "S12") (pin "1") (pinfunction "1_1") (pintype "input"))
      (node (ref "S9") (pin "1") (pinfunction "1_1") (pintype "input"))
    )
    (net (code "12") (name "COLOM4") (class "Default")
      (node (ref "RaspberryPiPico2W") (pin "7") (pinfunction "GP5_SPI0CSn_I2C0SCL_UART1RX_7") (pintype "unspecified"))
      (node (ref "S13") (pin "1") (pinfunction "1_1") (pintype "input"))
      (node (ref "S14") (pin "1") (pinfunction "1_1") (pintype "input"))
      (node (ref "S15") (pin "1") (pinfunction "1_1") (pintype "input"))
      (node (ref "S16") (pin "1") (pinfunction "1_1") (pintype "input"))
    )
    (net (code "13") (name "COLOM5") (class "Default")
      (node (ref "RaspberryPiPico2W") (pin "6") (pinfunction "GP4_SPI0RX_I2C0SDA_UART1TX_6") (pintype "unspecified"))
      (node (ref "S17") (pin "1") (pinfunction "1_1") (pintype "input"))
      (node (ref "S18") (pin "1") (pinfunction "1_1") (pintype "input"))
      (node (ref "S19") (pin "1") (pinfunction "1_1") (pintype "input"))
      (node (ref "S20") (pin "1") (pinfunction "1_1") (pintype "input"))
    )
    (net (code "14") (name "D+") (class "Default")
      (node (ref "RaspberryPiPico2W") (pin "TP3") (pinfunction "TP3_TP3") (pintype "unspecified"))
      (node (ref "USB1") (pin "A6") (pinfunction "Dp1_A6") (pintype "unspecified"))
      (node (ref "USB1") (pin "B6") (pinfunction "Dp2_B6") (pintype "unspecified"))
    )
    (net (code "15") (name "D-") (class "Default")
      (node (ref "RaspberryPiPico2W") (pin "TP2") (pinfunction "TP2_TP2") (pintype "unspecified"))
      (node (ref "USB1") (pin "A7") (pinfunction "Dn1_A7") (pintype "unspecified"))
      (node (ref "USB1") (pin "B7") (pinfunction "Dn2_B7") (pintype "unspecified"))
    )
    (net (code "16") (name "GND") (class "Default")
      (node (ref "Boot") (pin "2") (pinfunction "2_2") (pintype "unspecified"))
      (node (ref "C21") (pin "2") (pinfunction "2_2") (pintype "unspecified"))
      (node (ref "C22") (pin "2") (pinfunction "2_2") (pintype "unspecified"))
      (node (ref "C23") (pin "2") (pinfunction "2_2") (pintype "unspecified"))
      (node (ref "C24") (pin "2") (pinfunction "2_2") (pintype "unspecified"))
      (node (ref "C25") (pin "2") (pinfunction "2_2") (pintype "unspecified"))
      (node (ref "C26") (pin "2") (pinfunction "2_2") (pintype "unspecified"))
      (node (ref "C27") (pin "2") (pinfunction "2_2") (pintype "unspecified"))
      (node (ref "C28") (pin "2") (pinfunction "2_2") (pintype "unspecified"))
      (node (ref "C29") (pin "2") (pinfunction "2_2") (pintype "unspecified"))
      (node (ref "C30") (pin "2") (pinfunction "2_2") (pintype "unspecified"))
      (node (ref "C31") (pin "2") (pinfunction "2_2") (pintype "unspecified"))
      (node (ref "C32") (pin "2") (pinfunction "2_2") (pintype "unspecified"))
      (node (ref "C33") (pin "2") (pinfunction "2_2") (pintype "unspecified"))
      (node (ref "C34") (pin "2") (pinfunction "2_2") (pintype "unspecified"))
      (node (ref "C35") (pin "2") (pinfunction "2_2") (pintype "unspecified"))
      (node (ref "C36") (pin "2") (pinfunction "2_2") (pintype "unspecified"))
      (node (ref "C37") (pin "2") (pinfunction "2_2") (pintype "unspecified"))
      (node (ref "C38") (pin "2") (pinfunction "2_2") (pintype "unspecified"))
      (node (ref "C39") (pin "2") (pinfunction "2_2") (pintype "unspecified"))
      (node (ref "C40") (pin "2") (pinfunction "2_2") (pintype "unspecified"))
      (node (ref "C41") (pin "1") (pinfunction "1_1") (pintype "input"))
      (node (ref "C42") (pin "1") (pinfunction "1_1") (pintype "input"))
      (node (ref "C43") (pin "1") (pinfunction "1_1") (pintype "unspecified"))
      (node (ref "Encoder") (pin "C") (pinfunction "C_C") (pintype "unspecified"))
      (node (ref "Encoder") (pin "E") (pinfunction "E_E") (pintype "unspecified"))
      (node (ref "LED21") (pin "3") (pinfunction "GND_3") (pintype "unspecified"))
      (node (ref "LED22") (pin "3") (pinfunction "GND_3") (pintype "unspecified"))
      (node (ref "LED23") (pin "3") (pinfunction "GND_3") (pintype "unspecified"))
      (node (ref "LED24") (pin "3") (pinfunction "GND_3") (pintype "unspecified"))
      (node (ref "LED25") (pin "3") (pinfunction "GND_3") (pintype "unspecified"))
      (node (ref "LED26") (pin "3") (pinfunction "GND_3") (pintype "unspecified"))
      (node (ref "LED27") (pin "3") (pinfunction "GND_3") (pintype "unspecified"))
      (node (ref "LED28") (pin "3") (pinfunction "GND_3") (pintype "unspecified"))
      (node (ref "LED29") (pin "3") (pinfunction "GND_3") (pintype "unspecified"))
      (node (ref "LED30") (pin "3") (pinfunction "GND_3") (pintype "unspecified"))
      (node (ref "LED31") (pin "3") (pinfunction "GND_3") (pintype "unspecified"))
      (node (ref "LED32") (pin "3") (pinfunction "GND_3") (pintype "unspecified"))
      (node (ref "LED33") (pin "3") (pinfunction "GND_3") (pintype "unspecified"))
      (node (ref "LED34") (pin "3") (pinfunction "GND_3") (pintype "unspecified"))
      (node (ref "LED35") (pin "3") (pinfunction "GND_3") (pintype "unspecified"))
      (node (ref "LED36") (pin "3") (pinfunction "GND_3") (pintype "unspecified"))
      (node (ref "LED37") (pin "3") (pinfunction "GND_3") (pintype "unspecified"))
      (node (ref "LED38") (pin "3") (pinfunction "GND_3") (pintype "unspecified"))
      (node (ref "LED39") (pin "3") (pinfunction "GND_3") (pintype "unspecified"))
      (node (ref "LED40") (pin "3") (pinfunction "GND_3") (pintype "unspecified"))
      (node (ref "OLED_Female_P") (pin "3") (pinfunction "3_3") (pintype "input"))
      (node (ref "P2") (pin "2") (pinfunction "2_2") (pintype "input"))
      (node (ref "R1") (pin "1") (pinfunction "1_1") (pintype "unspecified"))
      (node (ref "R2") (pin "1") (pinfunction "1_1") (pintype "unspecified"))
      (node (ref "RESET") (pin "2") (pinfunction "2_2") (pintype "unspecified"))
      (node (ref "RaspberryPiPico2W") (pin "13") (pinfunction "GND_13") (pintype "unspecified"))
      (node (ref "RaspberryPiPico2W") (pin "18") (pinfunction "GND_18") (pintype "unspecified"))
      (node (ref "RaspberryPiPico2W") (pin "23") (pinfunction "GND_23") (pintype "unspecified"))
      (node (ref "RaspberryPiPico2W") (pin "28") (pinfunction "GND_28") (pintype "unspecified"))
      (node (ref "RaspberryPiPico2W") (pin "3") (pinfunction "GND_3") (pintype "unspecified"))
      (node (ref "RaspberryPiPico2W") (pin "38") (pinfunction "GND_38") (pintype "unspecified"))
      (node (ref "RaspberryPiPico2W") (pin "8") (pinfunction "GND_8") (pintype "unspecified"))
      (node (ref "RaspberryPiPico2W") (pin "TP1") (pinfunction "TP1_TP1") (pintype "unspecified"))
      (node (ref "U6") (pin "3") (pinfunction "GND_3") (pintype "input"))
      (node (ref "USB1") (pin "1") (pinfunction "EH_1") (pintype "unspecified"))
      (node (ref "USB1") (pin "2") (pinfunction "EH_2") (pintype "unspecified"))
      (node (ref "USB1") (pin "3") (pinfunction "EH_3") (pintype "unspecified"))
      (node (ref "USB1") (pin "4") (pinfunction "EH_4") (pintype "unspecified"))
      (node (ref "USB1") (pin "A1-B12") (pinfunction "GND_A1-B12") (pintype "unspecified"))
      (node (ref "USB1") (pin "B1-A12") (pinfunction "GND_B1-A12") (pintype "unspecified"))
    )
    (net (code "17") (name "LED_3.3") (class "Default")
      (node (ref "C43") (pin "2") (pinfunction "2_2") (pintype "unspecified"))
      (node (ref "RaspberryPiPico2W") (pin "12") (pinfunction "GP9_SPI1CSn_I2C0SCL_UART1RX_12") (pintype "unspecified"))
      (node (ref "U6") (pin "2") (pinfunction "A_2") (pintype "input"))
    )
    (net (code "18") (name "LED_5") (class "Default")
      (node (ref "LED40") (pin "4") (pinfunction "DIN_4") (pintype "unspecified"))
      (node (ref "R5") (pin "2") (pinfunction "2_2") (pintype "unspecified"))
    )
    (net (code "19") (name "Net-(D1-C)") (class "Default")
      (node (ref "D1") (pin "1") (pinfunction "C_1") (pintype "unspecified"))
      (node (ref "S1") (pin "2") (pinfunction "2_2") (pintype "input"))
    )
    (net (code "20") (name "Net-(D2-C)") (class "Default")
      (node (ref "D2") (pin "1") (pinfunction "C_1") (pintype "unspecified"))
      (node (ref "S2") (pin "2") (pinfunction "2_2") (pintype "input"))
    )
    (net (code "21") (name "Net-(D3-C)") (class "Default")
      (node (ref "D3") (pin "1") (pinfunction "C_1") (pintype "unspecified"))
      (node (ref "S3") (pin "2") (pinfunction "2_2") (pintype "input"))
    )
    (net (code "22") (name "Net-(D4-C)") (class "Default")
      (node (ref "D4") (pin "1") (pinfunction "C_1") (pintype "unspecified"))
      (node (ref "S4") (pin "2") (pinfunction "2_2") (pintype "input"))
    )
    (net (code "23") (name "Net-(D5-C)") (class "Default")
      (node (ref "D5") (pin "1") (pinfunction "C_1") (pintype "unspecified"))
      (node (ref "S5") (pin "2") (pinfunction "2_2") (pintype "input"))
    )
    (net (code "24") (name "Net-(D6-C)") (class "Default")
      (node (ref "D6") (pin "1") (pinfunction "C_1") (pintype "unspecified"))
      (node (ref "S6") (pin "2") (pinfunction "2_2") (pintype "input"))
    )
    (net (code "25") (name "Net-(D7-C)") (class "Default")
      (node (ref "D7") (pin "1") (pinfunction "C_1") (pintype "unspecified"))
      (node (ref "S7") (pin "2") (pinfunction "2_2") (pintype "input"))
    )
    (net (code "26") (name "Net-(D8-C)") (class "Default")
      (node (ref "D8") (pin "1") (pinfunction "C_1") (pintype "unspecified"))
      (node (ref "S8") (pin "2") (pinfunction "2_2") (pintype "input"))
    )
    (net (code "27") (name "Net-(D9-C)") (class "Default")
      (node (ref "D9") (pin "1") (pinfunction "C_1") (pintype "unspecified"))
      (node (ref "S9") (pin "2") (pinfunction "2_2") (pintype "input"))
    )
    (net (code "28") (name "Net-(D10-C)") (class "Default")
      (node (ref "D10") (pin "1") (pinfunction "C_1") (pintype "unspecified"))
      (node (ref "S10") (pin "2") (pinfunction "2_2") (pintype "input"))
    )
    (net (code "29") (name "Net-(D11-C)") (class "Default")
      (node (ref "D11") (pin "1") (pinfunction "C_1") (pintype "unspecified"))
      (node (ref "S11") (pin "2") (pinfunction "2_2") (pintype "input"))
    )
    (net (code "30") (name "Net-(D12-C)") (class "Default")
      (node (ref "D12") (pin "1") (pinfunction "C_1") (pintype "unspecified"))
      (node (ref "S12") (pin "2") (pinfunction "2_2") (pintype "input"))
    )
    (net (code "31") (name "Net-(D13-C)") (class "Default")
      (node (ref "D13") (pin "1") (pinfunction "C_1") (pintype "unspecified"))
      (node (ref "S13") (pin "2") (pinfunction "2_2") (pintype "input"))
    )
    (net (code "32") (name "Net-(D14-C)") (class "Default")
      (node (ref "D14") (pin "1") (pinfunction "C_1") (pintype "unspecified"))
      (node (ref "S14") (pin "2") (pinfunction "2_2") (pintype "input"))
    )
    (net (code "33") (name "Net-(D15-C)") (class "Default")
      (node (ref "D15") (pin "1") (pinfunction "C_1") (pintype "unspecified"))
      (node (ref "S15") (pin "2") (pinfunction "2_2") (pintype "input"))
    )
    (net (code "34") (name "Net-(D16-C)") (class "Default")
      (node (ref "D16") (pin "1") (pinfunction "C_1") (pintype "unspecified"))
      (node (ref "S16") (pin "2") (pinfunction "2_2") (pintype "input"))
    )
    (net (code "35") (name "Net-(D17-C)") (class "Default")
      (node (ref "D17") (pin "1") (pinfunction "C_1") (pintype "unspecified"))
      (node (ref "S17") (pin "2") (pinfunction "2_2") (pintype "input"))
    )
    (net (code "36") (name "Net-(D18-C)") (class "Default")
      (node (ref "D18") (pin "1") (pinfunction "C_1") (pintype "unspecified"))
      (node (ref "S18") (pin "2") (pinfunction "2_2") (pintype "input"))
    )
    (net (code "37") (name "Net-(D19-C)") (class "Default")
      (node (ref "D19") (pin "1") (pinfunction "C_1") (pintype "unspecified"))
      (node (ref "S19") (pin "2") (pinfunction "2_2") (pintype "input"))
    )
    (net (code "38") (name "Net-(D20-C)") (class "Default")
      (node (ref "D20") (pin "1") (pinfunction "C_1") (pintype "unspecified"))
      (node (ref "S20") (pin "2") (pinfunction "2_2") (pintype "input"))
    )
    (net (code "39") (name "Net-(LED21-DIN)") (class "Default")
      (node (ref "LED21") (pin "4") (pinfunction "DIN_4") (pintype "unspecified"))
      (node (ref "LED22") (pin "2") (pinfunction "DOUT_2") (pintype "unspecified"))
    )
    (net (code "40") (name "Net-(LED22-DIN)") (class "Default")
      (node (ref "LED22") (pin "4") (pinfunction "DIN_4") (pintype "unspecified"))
      (node (ref "LED23") (pin "2") (pinfunction "DOUT_2") (pintype "unspecified"))
    )
    (net (code "41") (name "Net-(LED23-DIN)") (class "Default")
      (node (ref "LED23") (pin "4") (pinfunction "DIN_4") (pintype "unspecified"))
      (node (ref "LED24") (pin "2") (pinfunction "DOUT_2") (pintype "unspecified"))
    )
    (net (code "42") (name "Net-(LED24-DIN)") (class "Default")
      (node (ref "LED24") (pin "4") (pinfunction "DIN_4") (pintype "unspecified"))
      (node (ref "LED25") (pin "2") (pinfunction "DOUT_2") (pintype "unspecified"))
    )
    (net (code "43") (name "Net-(LED25-DIN)") (class "Default")
      (node (ref "LED25") (pin "4") (pinfunction "DIN_4") (pintype "unspecified"))
      (node (ref "LED26") (pin "2") (pinfunction "DOUT_2") (pintype "unspecified"))
    )
    (net (code "44") (name "Net-(LED26-DIN)") (class "Default")
      (node (ref "LED26") (pin "4") (pinfunction "DIN_4") (pintype "unspecified"))
      (node (ref "LED27") (pin "2") (pinfunction "DOUT_2") (pintype "unspecified"))
    )
    (net (code "45") (name "Net-(LED27-DIN)") (class "Default")
      (node (ref "LED27") (pin "4") (pinfunction "DIN_4") (pintype "unspecified"))
      (node (ref "LED28") (pin "2") (pinfunction "DOUT_2") (pintype "unspecified"))
    )
    (net (code "46") (name "Net-(LED28-DIN)") (class "Default")
      (node (ref "LED28") (pin "4") (pinfunction "DIN_4") (pintype "unspecified"))
      (node (ref "LED29") (pin "2") (pinfunction "DOUT_2") (pintype "unspecified"))
    )
    (net (code "47") (name "Net-(LED29-DIN)") (class "Default")
      (node (ref "LED29") (pin "4") (pinfunction "DIN_4") (pintype "unspecified"))
      (node (ref "LED30") (pin "2") (pinfunction "DOUT_2") (pintype "unspecified"))
    )
    (net (code "48") (name "Net-(LED30-DIN)") (class "Default")
      (node (ref "LED30") (pin "4") (pinfunction "DIN_4") (pintype "unspecified"))
      (node (ref "LED31") (pin "2") (pinfunction "DOUT_2") (pintype "unspecified"))
    )
    (net (code "49") (name "Net-(LED31-DIN)") (class "Default")
      (node (ref "LED31") (pin "4") (pinfunction "DIN_4") (pintype "unspecified"))
      (node (ref "LED32") (pin "2") (pinfunction "DOUT_2") (pintype "unspecified"))
    )
    (net (code "50") (name "Net-(LED32-DIN)") (class "Default")
      (node (ref "LED32") (pin "4") (pinfunction "DIN_4") (pintype "unspecified"))
      (node (ref "LED33") (pin "2") (pinfunction "DOUT_2") (pintype "unspecified"))
    )
    (net (code "51") (name "Net-(LED33-DIN)") (class "Default")
      (node (ref "LED33") (pin "4") (pinfunction "DIN_4") (pintype "unspecified"))
      (node (ref "LED34") (pin "2") (pinfunction "DOUT_2") (pintype "unspecified"))
    )
    (net (code "52") (name "Net-(LED34-DIN)") (class "Default")
      (node (ref "LED34") (pin "4") (pinfunction "DIN_4") (pintype "unspecified"))
      (node (ref "LED35") (pin "2") (pinfunction "DOUT_2") (pintype "unspecified"))
    )
    (net (code "53") (name "Net-(LED35-DIN)") (class "Default")
      (node (ref "LED35") (pin "4") (pinfunction "DIN_4") (pintype "unspecified"))
      (node (ref "LED36") (pin "2") (pinfunction "DOUT_2") (pintype "unspecified"))
    )
    (net (code "54") (name "Net-(LED36-DIN)") (class "Default")
      (node (ref "LED36") (pin "4") (pinfunction "DIN_4") (pintype "unspecified"))
      (node (ref "LED37") (pin "2") (pinfunction "DOUT_2") (pintype "unspecified"))
    )
    (net (code "55") (name "Net-(LED37-DIN)") (class "Default")
      (node (ref "LED37") (pin "4") (pinfunction "DIN_4") (pintype "unspecified"))
      (node (ref "LED38") (pin "2") (pinfunction "DOUT_2") (pintype "unspecified"))
    )
    (net (code "56") (name "Net-(LED38-DIN)") (class "Default")
      (node (ref "LED38") (pin "4") (pinfunction "DIN_4") (pintype "unspecified"))
      (node (ref "LED39") (pin "2") (pinfunction "DOUT_2") (pintype "unspecified"))
    )
    (net (code "57") (name "Net-(LED39-DIN)") (class "Default")
      (node (ref "LED39") (pin "4") (pinfunction "DIN_4") (pintype "unspecified"))
      (node (ref "LED40") (pin "2") (pinfunction "DOUT_2") (pintype "unspecified"))
    )
    (net (code "58") (name "Net-(P2-Pad1)") (class "Default")
      (node (ref "P2") (pin "1") (pinfunction "1_1") (pintype "input"))
      (node (ref "P3") (pin "1") (pinfunction "1_1") (pintype "input"))
      (node (ref "Volume_Slider") (pin "1") (pinfunction "1_1") (pintype "unspecified"))
    )
    (net (code "59") (name "Net-(U6-Y)") (class "Default")
      (node (ref "R5") (pin "1") (pinfunction "1_1") (pintype "unspecified"))
      (node (ref "U6") (pin "4") (pinfunction "Y_4") (pintype "input"))
    )
    (net (code "60") (name "Net-(USB1-CC1)") (class "Default")
      (node (ref "R1") (pin "2") (pinfunction "2_2") (pintype "unspecified"))
      (node (ref "USB1") (pin "A5") (pinfunction "CC1_A5") (pintype "unspecified"))
    )
    (net (code "61") (name "Net-(USB1-CC2)") (class "Default")
      (node (ref "R2") (pin "2") (pinfunction "2_2") (pintype "unspecified"))
      (node (ref "USB1") (pin "B5") (pinfunction "CC2_B5") (pintype "unspecified"))
    )
    (net (code "62") (name "RESET") (class "Default")
      (node (ref "RESET") (pin "1") (pinfunction "1_1") (pintype "unspecified"))
      (node (ref "RaspberryPiPico2W") (pin "30") (pinfunction "RUN_30") (pintype "unspecified"))
    )
    (net (code "63") (name "ROW1") (class "Default")
      (node (ref "D1") (pin "2") (pinfunction "A_2") (pintype "unspecified"))
      (node (ref "D13") (pin "2") (pinfunction "A_2") (pintype "unspecified"))
      (node (ref "D17") (pin "2") (pinfunction "A_2") (pintype "unspecified"))
      (node (ref "D5") (pin "2") (pinfunction "A_2") (pintype "unspecified"))
      (node (ref "D9") (pin "2") (pinfunction "A_2") (pintype "unspecified"))
      (node (ref "RaspberryPiPico2W") (pin "1") (pinfunction "GP0_SPI0RX_I2C0SDA_UART0TX_1") (pintype "unspecified"))
    )
    (net (code "64") (name "ROW2") (class "Default")
      (node (ref "D10") (pin "2") (pinfunction "A_2") (pintype "unspecified"))
      (node (ref "D14") (pin "2") (pinfunction "A_2") (pintype "unspecified"))
      (node (ref "D18") (pin "2") (pinfunction "A_2") (pintype "unspecified"))
      (node (ref "D2") (pin "2") (pinfunction "A_2") (pintype "unspecified"))
      (node (ref "D6") (pin "2") (pinfunction "A_2") (pintype "unspecified"))
      (node (ref "RaspberryPiPico2W") (pin "2") (pinfunction "GP1_SPI0CSn_I2C0SCL_UART0RX_2") (pintype "unspecified"))
    )
    (net (code "65") (name "ROW3") (class "Default")
      (node (ref "D11") (pin "2") (pinfunction "A_2") (pintype "unspecified"))
      (node (ref "D15") (pin "2") (pinfunction "A_2") (pintype "unspecified"))
      (node (ref "D19") (pin "2") (pinfunction "A_2") (pintype "unspecified"))
      (node (ref "D3") (pin "2") (pinfunction "A_2") (pintype "unspecified"))
      (node (ref "D7") (pin "2") (pinfunction "A_2") (pintype "unspecified"))
      (node (ref "RaspberryPiPico2W") (pin "4") (pinfunction "GP2_SPI0SCK_I2C1SDA_4") (pintype "unspecified"))
    )
    (net (code "66") (name "ROW4") (class "Default")
      (node (ref "D12") (pin "2") (pinfunction "A_2") (pintype "unspecified"))
      (node (ref "D16") (pin "2") (pinfunction "A_2") (pintype "unspecified"))
      (node (ref "D20") (pin "2") (pinfunction "A_2") (pintype "unspecified"))
      (node (ref "D4") (pin "2") (pinfunction "A_2") (pintype "unspecified"))
      (node (ref "D8") (pin "2") (pinfunction "A_2") (pintype "unspecified"))
      (node (ref "RaspberryPiPico2W") (pin "5") (pinfunction "GP3_SPI0TX_I2C1SCL_5") (pintype "unspecified"))
    )
    (net (code "67") (name "SCL") (class "Default")
      (node (ref "RaspberryPiPico2W") (pin "17") (pinfunction "GP13_SPI1CSn_I2C0SCL_UART0RX_17") (pintype "unspecified"))
    )
    (net (code "68") (name "SCL1") (class "Default")
      (node (ref "OLED_Female_P") (pin "2") (pinfunction "2_2") (pintype "input"))
      (node (ref "RaspberryPiPico2W") (pin "27") (pinfunction "GP21_I2C0SCL_27") (pintype "unspecified"))
    )
    (net (code "69") (name "SDA") (class "Default")
      (node (ref "RaspberryPiPico2W") (pin "16") (pinfunction "GP12_SPI1RX_I2C0SDA_UART0TX_16") (pintype "unspecified"))
    )
    (net (code "70") (name "SDA1") (class "Default")
      (node (ref "OLED_Female_P") (pin "1") (pinfunction "1_1") (pintype "input"))
      (node (ref "RaspberryPiPico2W") (pin "26") (pinfunction "GP20_I2C0SDA_26") (pintype "unspecified"))
    )
    (net (code "71") (name "SLIDER") (class "Default")
      (node (ref "RaspberryPiPico2W") (pin "34") (pinfunction "GP28_ADC2_34") (pintype "unspecified"))
      (node (ref "Volume_Slider") (pin "2") (pinfunction "2_2") (pintype "unspecified"))
    )
    (net (code "72") (name "SW1A") (class "Default")
      (node (ref "C42") (pin "2") (pinfunction "2_2") (pintype "input"))
      (node (ref "Encoder") (pin "A") (pinfunction "A_A") (pintype "unspecified"))
      (node (ref "R4") (pin "2") (pinfunction "2_2") (pintype "unspecified"))
      (node (ref "RaspberryPiPico2W") (pin "14") (pinfunction "GP10_SPI1SCK_I2C1SDA_14") (pintype "unspecified"))
    )
    (net (code "73") (name "SW1B") (class "Default")
      (node (ref "C41") (pin "2") (pinfunction "2_2") (pintype "input"))
      (node (ref "Encoder") (pin "B") (pinfunction "B_B") (pintype "unspecified"))
      (node (ref "R3") (pin "1") (pinfunction "1_1") (pintype "unspecified"))
      (node (ref "RaspberryPiPico2W") (pin "15") (pinfunction "GP11_SPI1TX_I2C1SCL_15") (pintype "unspecified"))
    )
    (net (code "74") (name "unconnected-(Encoder-Pad6)") (class "Default")
      (node (ref "Encoder") (pin "6") (pinfunction "6_6") (pintype "unspecified+no_connect"))
    )
    (net (code "75") (name "unconnected-(Encoder-Pad7)") (class "Default")
      (node (ref "Encoder") (pin "7") (pinfunction "7_7") (pintype "unspecified+no_connect"))
    )
    (net (code "76") (name "unconnected-(LED21-DOUT-Pad2)") (class "Default")
      (node (ref "LED21") (pin "2") (pinfunction "DOUT_2") (pintype "unspecified"))
    )
    (net (code "77") (name "unconnected-(RaspberryPiPico2W-3V3_EN-Pad37)") (class "Default")
      (node (ref "RaspberryPiPico2W") (pin "37") (pinfunction "3V3_EN_37") (pintype "unspecified"))
    )
    (net (code "78") (name "unconnected-(RaspberryPiPico2W-ADC_VREF-Pad35)") (class "Default")
      (node (ref "RaspberryPiPico2W") (pin "35") (pinfunction "ADC_VREF_35") (pintype "unspecified"))
    )
    (net (code "79") (name "unconnected-(RaspberryPiPico2W-GP15_SPI1TX_I2C1SCL-Pad20)") (class "Default")
      (node (ref "RaspberryPiPico2W") (pin "20") (pinfunction "GP15_SPI1TX_I2C1SCL_20") (pintype "unspecified"))
    )
    (net (code "80") (name "unconnected-(RaspberryPiPico2W-GP16_SPI0RX_UART0RX-Pad21)") (class "Default")
      (node (ref "RaspberryPiPico2W") (pin "21") (pinfunction "GP16_SPI0RX_UART0RX_21") (pintype "unspecified"))
    )
    (net (code "81") (name "unconnected-(RaspberryPiPico2W-GP17_SPI0CSn_UART0TX-Pad22)") (class "Default")
      (node (ref "RaspberryPiPico2W") (pin "22") (pinfunction "GP17_SPI0CSn_UART0TX_22") (pintype "unspecified"))
    )
    (net (code "82") (name "unconnected-(RaspberryPiPico2W-GP18_SPI0SCK_I2C1SDA-Pad24)") (class "Default")
      (node (ref "RaspberryPiPico2W") (pin "24") (pinfunction "GP18_SPI0SCK_I2C1SDA_24") (pintype "unspecified"))
    )
    (net (code "83") (name "unconnected-(RaspberryPiPico2W-GP19_SPI0TX_I2C1SCL-Pad25)") (class "Default")
      (node (ref "RaspberryPiPico2W") (pin "25") (pinfunction "GP19_SPI0TX_I2C1SCL_25") (pintype "unspecified"))
    )
    (net (code "84") (name "unconnected-(RaspberryPiPico2W-GP22-Pad29)") (class "Default")
      (node (ref "RaspberryPiPico2W") (pin "29") (pinfunction "GP22_29") (pintype "unspecified"))
    )
    (net (code "85") (name "unconnected-(RaspberryPiPico2W-PadTP4)") (class "Default")
      (node (ref "RaspberryPiPico2W") (pin "TP4") (pinfunction "TP4_TP4") (pintype "unspecified"))
    )
    (net (code "86") (name "unconnected-(RaspberryPiPico2W-PadTP5)") (class "Default")
      (node (ref "RaspberryPiPico2W") (pin "TP5") (pinfunction "TP5_TP5") (pintype "unspecified"))
    )
    (net (code "87") (name "unconnected-(RaspberryPiPico2W-VSYS-Pad39)") (class "Default")
      (node (ref "RaspberryPiPico2W") (pin "39") (pinfunction "VSYS_39") (pintype "unspecified"))
    )
    (net (code "88") (name "unconnected-(USB1-SBU1-PadA8)") (class "Default")
      (node (ref "USB1") (pin "A8") (pinfunction "SBU1_A8") (pintype "unspecified+no_connect"))
    )
    (net (code "89") (name "unconnected-(USB1-SBU2-PadB8)") (class "Default")
      (node (ref "USB1") (pin "B8") (pinfunction "SBU2_B8") (pintype "unspecified+no_connect"))
    )
    (net (code "90") (name "unconnected-(Volume_Slider-Pad4)") (class "Default")
      (node (ref "Volume_Slider") (pin "4") (pinfunction "4_4") (pintype "unspecified+no_connect"))
    )
    (net (code "91") (name "unconnected-(Volume_Slider-Pad5)") (class "Default")
      (node (ref "Volume_Slider") (pin "5") (pinfunction "5_5") (pintype "unspecified+no_connect"))
    )
    (net (code "92") (name "unconnected-(Volume_Slider-Pad6)") (class "Default")
      (node (ref "Volume_Slider") (pin "6") (pinfunction "6_6") (pintype "unspecified+no_connect"))
    )
    (net (code "93") (name "unconnected-(Volume_Slider-Pad7)") (class "Default")
      (node (ref "Volume_Slider") (pin "7") (pinfunction "7_7") (pintype "unspecified+no_connect"))
    )
  )
)
